# rev3.net
KiCad netlist of a schematic drawn in EAGLE
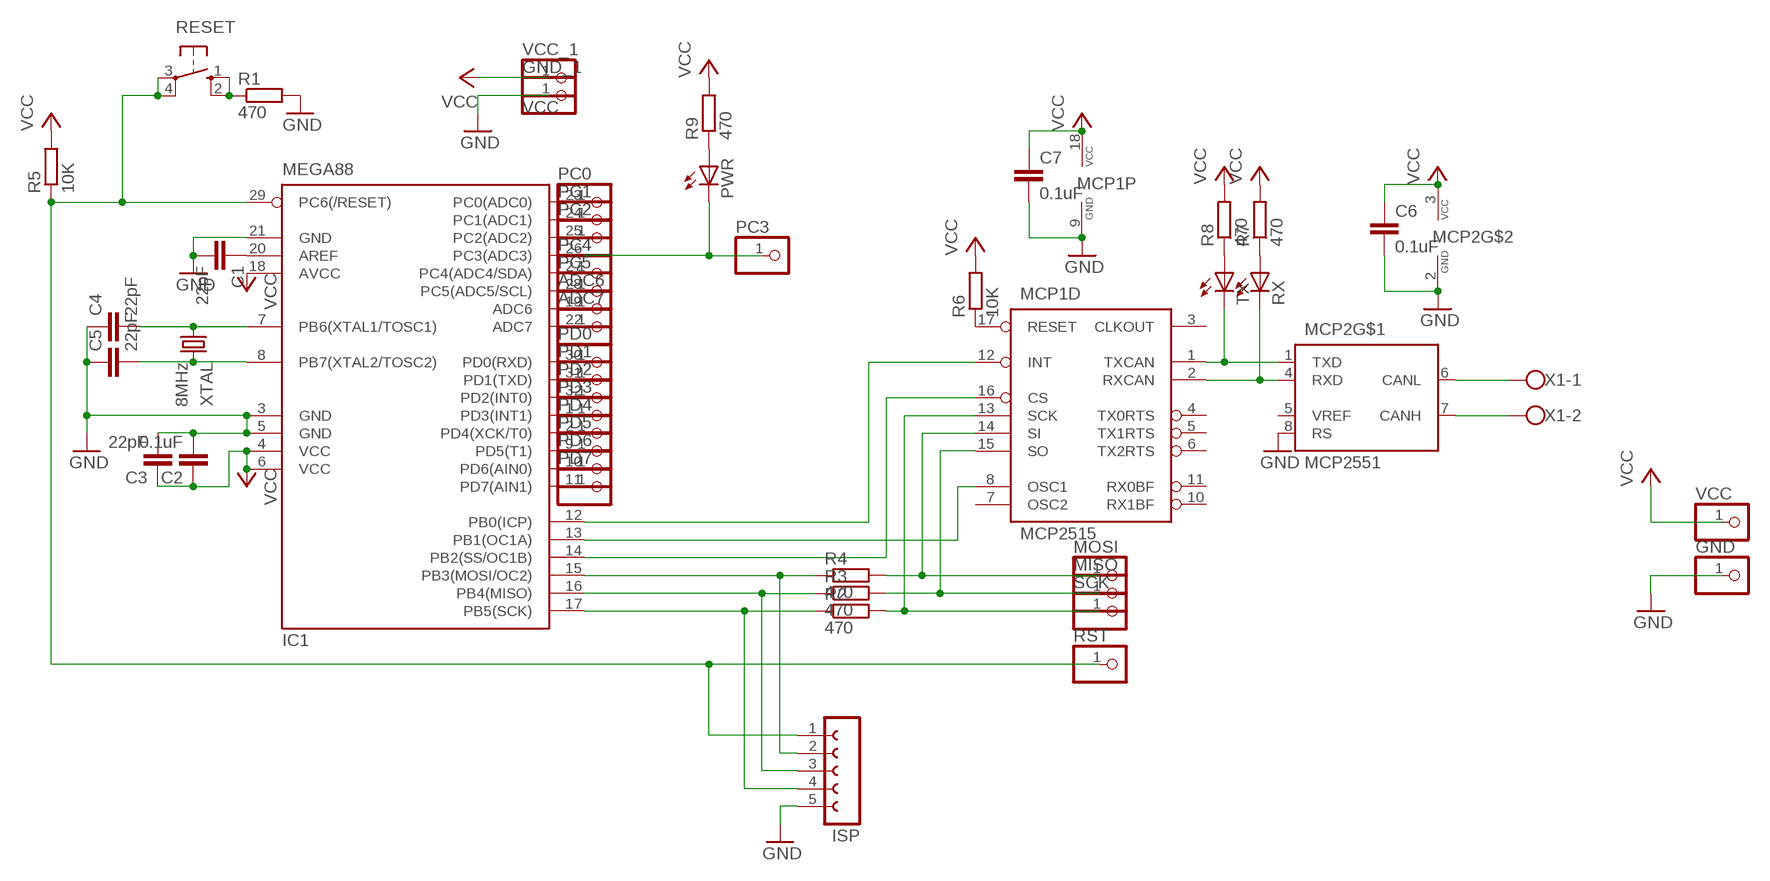
[diagram p0: schematic, sheet 1]

(export (version "E")
  (design (tool "Eeschema 10.0.6"))
  (components
    (comp (ref "ADC6")
      (value "PINHD-1X1")
      (footprint "eagle-import:1X01")
      (libsource (lib "eagle-import") (part "PINHD-1X1"))
    )
    (comp (ref "ADC7")
      (value "PINHD-1X1")
      (footprint "eagle-import:1X01")
      (libsource (lib "eagle-import") (part "PINHD-1X1"))
    )
    (comp (ref "C1")
      (value "22pF")
      (footprint "eagle-import:C0603")
      (libsource (lib "eagle-import") (part "C-EUC0603"))
    )
    (comp (ref "C2")
      (value "0.1uF")
      (footprint "eagle-import:C0603")
      (libsource (lib "eagle-import") (part "C-EUC0603"))
    )
    (comp (ref "C3")
      (value "22pF")
      (footprint "eagle-import:C0603")
      (libsource (lib "eagle-import") (part "C-EUC0603"))
    )
    (comp (ref "C4")
      (value "22pF")
      (footprint "eagle-import:C0603")
      (libsource (lib "eagle-import") (part "C-EUC0603"))
    )
    (comp (ref "C5")
      (value "22pF")
      (footprint "eagle-import:C0603")
      (libsource (lib "eagle-import") (part "C-EUC0603"))
    )
    (comp (ref "C6")
      (value "0.1uF")
      (footprint "eagle-import:C0603")
      (libsource (lib "eagle-import") (part "C-EUC0603"))
    )
    (comp (ref "C7")
      (value "0.1uF")
      (footprint "eagle-import:C0603")
      (libsource (lib "eagle-import") (part "C-EUC0603"))
    )
    (comp (ref "GND")
      (value "PINHD-1X1")
      (footprint "eagle-import:1X01")
      (libsource (lib "eagle-import") (part "PINHD-1X1"))
    )
    (comp (ref "GND_1")
      (value "PINHD-1X1")
      (footprint "eagle-import:1X01")
      (libsource (lib "eagle-import") (part "PINHD-1X1"))
    )
    (comp (ref "IC1")
      (value "MEGA88")
      (footprint "eagle-import:TQFP32-08")
      (fields (field (name "MPN") "ATMEGA8-16AU") (field (name "OC_NEWARK") "unknown"))
      (libsource (lib "eagle-import") (part "MEGA8-AI"))
    )
    (comp (ref "ISP")
      (value "FE05-1")
      (footprint "eagle-import:FE05-1")
      (libsource (lib "eagle-import") (part "FE05-1"))
    )
    (comp (ref "MCP1")
      (value "MCP2515")
      (footprint "eagle-import:DIL18")
      (fields (field (name "OC_NEWARK") "unknown"))
      (libsource (lib "eagle-import") (part "MCP2515P"))
    )
    (comp (ref "MCP2")
      (value "MCP2551")
      (footprint "eagle-import:DIL08")
      (fields (field (name "OC_NEWARK") "unknown"))
      (libsource (lib "eagle-import") (part "MCP2551DIL8"))
    )
    (comp (ref "MISO")
      (value "PINHD-1X1")
      (footprint "eagle-import:1X01")
      (libsource (lib "eagle-import") (part "PINHD-1X1"))
    )
    (comp (ref "MOSI")
      (value "PINHD-1X1")
      (footprint "eagle-import:1X01")
      (libsource (lib "eagle-import") (part "PINHD-1X1"))
    )
    (comp (ref "PC0")
      (value "PINHD-1X1")
      (footprint "eagle-import:1X01")
      (libsource (lib "eagle-import") (part "PINHD-1X1"))
    )
    (comp (ref "PC1")
      (value "PINHD-1X1")
      (footprint "eagle-import:1X01")
      (libsource (lib "eagle-import") (part "PINHD-1X1"))
    )
    (comp (ref "PC2")
      (value "PINHD-1X1")
      (footprint "eagle-import:1X01")
      (libsource (lib "eagle-import") (part "PINHD-1X1"))
    )
    (comp (ref "PC3")
      (value "PINHD-1X1")
      (footprint "eagle-import:1X01")
      (libsource (lib "eagle-import") (part "PINHD-1X1"))
    )
    (comp (ref "PC4")
      (value "PINHD-1X1")
      (footprint "eagle-import:1X01")
      (libsource (lib "eagle-import") (part "PINHD-1X1"))
    )
    (comp (ref "PC5")
      (value "PINHD-1X1")
      (footprint "eagle-import:1X01")
      (libsource (lib "eagle-import") (part "PINHD-1X1"))
    )
    (comp (ref "PD0")
      (value "PINHD-1X1")
      (footprint "eagle-import:1X01")
      (libsource (lib "eagle-import") (part "PINHD-1X1"))
    )
    (comp (ref "PD1")
      (value "PINHD-1X1")
      (footprint "eagle-import:1X01")
      (libsource (lib "eagle-import") (part "PINHD-1X1"))
    )
    (comp (ref "PD2")
      (value "PINHD-1X1")
      (footprint "eagle-import:1X01")
      (libsource (lib "eagle-import") (part "PINHD-1X1"))
    )
    (comp (ref "PD3")
      (value "PINHD-1X1")
      (footprint "eagle-import:1X01")
      (libsource (lib "eagle-import") (part "PINHD-1X1"))
    )
    (comp (ref "PD4")
      (value "PINHD-1X1")
      (footprint "eagle-import:1X01")
      (libsource (lib "eagle-import") (part "PINHD-1X1"))
    )
    (comp (ref "PD5")
      (value "PINHD-1X1")
      (footprint "eagle-import:1X01")
      (libsource (lib "eagle-import") (part "PINHD-1X1"))
    )
    (comp (ref "PD6")
      (value "PINHD-1X1")
      (footprint "eagle-import:1X01")
      (libsource (lib "eagle-import") (part "PINHD-1X1"))
    )
    (comp (ref "PD7")
      (value "PINHD-1X1")
      (footprint "eagle-import:1X01")
      (libsource (lib "eagle-import") (part "PINHD-1X1"))
    )
    (comp (ref "PWR")
      (value "LEDCHIP-LED0603")
      (footprint "eagle-import:CHIP-LED0603")
      (libsource (lib "eagle-import") (part "LEDCHIP-LED0603"))
    )
    (comp (ref "R1")
      (value "470")
      (footprint "eagle-import:R0603")
      (libsource (lib "eagle-import") (part "R-EU_R0603"))
    )
    (comp (ref "R2")
      (value "470")
      (footprint "eagle-import:R0603")
      (libsource (lib "eagle-import") (part "R-EU_R0603"))
    )
    (comp (ref "R3")
      (value "470")
      (footprint "eagle-import:R0603")
      (libsource (lib "eagle-import") (part "R-EU_R0603"))
    )
    (comp (ref "R4")
      (value "470")
      (footprint "eagle-import:R0603")
      (libsource (lib "eagle-import") (part "R-EU_R0603"))
    )
    (comp (ref "R5")
      (value "10K")
      (footprint "eagle-import:R0603")
      (libsource (lib "eagle-import") (part "R-EU_R0603"))
    )
    (comp (ref "R6")
      (value "10K")
      (footprint "eagle-import:R0603")
      (libsource (lib "eagle-import") (part "R-EU_R0603"))
    )
    (comp (ref "R7")
      (value "470")
      (footprint "eagle-import:R0603")
      (libsource (lib "eagle-import") (part "R-EU_R0603"))
    )
    (comp (ref "R8")
      (value "470")
      (footprint "eagle-import:R0603")
      (libsource (lib "eagle-import") (part "R-EU_R0603"))
    )
    (comp (ref "R9")
      (value "470")
      (footprint "eagle-import:R0603")
      (libsource (lib "eagle-import") (part "R-EU_R0603"))
    )
    (comp (ref "RESET")
      (value "10-XX")
      (footprint "eagle-import:B3F-10XX")
      (fields (field (name "MPN") "B3F-1000"))
      (libsource (lib "eagle-import") (part "10-XX"))
    )
    (comp (ref "RST")
      (value "PINHD-1X1")
      (footprint "eagle-import:1X01")
      (libsource (lib "eagle-import") (part "PINHD-1X1"))
    )
    (comp (ref "RX")
      (value "LEDCHIP-LED0603")
      (footprint "eagle-import:CHIP-LED0603")
      (libsource (lib "eagle-import") (part "LEDCHIP-LED0603"))
    )
    (comp (ref "SCK")
      (value "PINHD-1X1")
      (footprint "eagle-import:1X01")
      (libsource (lib "eagle-import") (part "PINHD-1X1"))
    )
    (comp (ref "TX")
      (value "LEDCHIP-LED0603")
      (footprint "eagle-import:CHIP-LED0603")
      (libsource (lib "eagle-import") (part "LEDCHIP-LED0603"))
    )
    (comp (ref "VCC")
      (value "PINHD-1X1")
      (footprint "eagle-import:1X01")
      (libsource (lib "eagle-import") (part "PINHD-1X1"))
    )
    (comp (ref "VCC_1")
      (value "VCC")
      (footprint "eagle-import:1X01")
      (libsource (lib "eagle-import") (part "PINHD-1X1"))
    )
    (comp (ref "X1")
      (value "W237-102")
      (footprint "eagle-import:W237-102")
      (fields (field (name "MPN") "237-102"))
      (libsource (lib "eagle-import") (part "W237-102"))
    )
    (comp (ref "XTAL")
      (value "8MHz")
      (footprint "eagle-import:HC49_S")
      (fields (field (name "OC_NEWARK") "unknown"))
      (libsource (lib "eagle-import") (part "CRYSTALHC49S"))
    )
  )
  (nets
    (net (code "1") (name "GND") (class "Default")
      (node (ref "C1") (pin "2") (pinfunction "2_2") (pintype "passive"))
      (node (ref "C2") (pin "2") (pinfunction "2_2") (pintype "passive"))
      (node (ref "C3") (pin "2") (pinfunction "2_2") (pintype "passive"))
      (node (ref "C4") (pin "1") (pinfunction "1_1") (pintype "passive"))
      (node (ref "C5") (pin "1") (pinfunction "1_1") (pintype "passive"))
      (node (ref "C6") (pin "2") (pinfunction "2_2") (pintype "passive"))
      (node (ref "C7") (pin "2") (pinfunction "2_2") (pintype "passive"))
      (node (ref "GND") (pin "1") (pinfunction "1_1") (pintype "passive"))
      (node (ref "GND_1") (pin "1") (pinfunction "1_1") (pintype "passive"))
      (node (ref "IC1") (pin "21") (pinfunction "GND_21") (pintype "power_in"))
      (node (ref "IC1") (pin "3") (pinfunction "GND_3") (pintype "power_in"))
      (node (ref "IC1") (pin "5") (pinfunction "GND_5") (pintype "power_in"))
      (node (ref "ISP") (pin "5") (pinfunction "5_5") (pintype "passive"))
      (node (ref "MCP1") (pin "9") (pinfunction "GND_9") (pintype "power_in"))
      (node (ref "MCP2") (pin "2") (pinfunction "GND_2") (pintype "power_in"))
      (node (ref "MCP2") (pin "8") (pinfunction "RS_8") (pintype "bidirectional"))
      (node (ref "R1") (pin "2") (pinfunction "2_2") (pintype "passive"))
    )
    (net (code "2") (name "Net-(IC1-ADC6)") (class "Default")
      (node (ref "ADC6") (pin "1") (pinfunction "1_1") (pintype "passive"))
      (node (ref "IC1") (pin "19") (pinfunction "ADC6_19") (pintype "bidirectional"))
    )
    (net (code "3") (name "Net-(IC1-ADC7)") (class "Default")
      (node (ref "ADC7") (pin "1") (pinfunction "1_1") (pintype "passive"))
      (node (ref "IC1") (pin "22") (pinfunction "ADC7_22") (pintype "bidirectional"))
    )
    (net (code "4") (name "Net-(IC1-AREF)") (class "Default")
      (node (ref "C1") (pin "1") (pinfunction "1_1") (pintype "passive"))
      (node (ref "IC1") (pin "20") (pinfunction "AREF_20") (pintype "passive"))
    )
    (net (code "5") (name "Net-(IC1-PB0(ICP))") (class "Default")
      (node (ref "IC1") (pin "12") (pinfunction "PB0(ICP)_12") (pintype "bidirectional"))
      (node (ref "MCP1") (pin "12") (pinfunction "INT_12") (pintype "output"))
    )
    (net (code "6") (name "Net-(IC1-PB1(OC1A))") (class "Default")
      (node (ref "IC1") (pin "13") (pinfunction "PB1(OC1A)_13") (pintype "bidirectional"))
      (node (ref "MCP1") (pin "8") (pinfunction "OSC1_8") (pintype "input"))
    )
    (net (code "7") (name "Net-(IC1-PB2(SS{slash}OC1B))") (class "Default")
      (node (ref "IC1") (pin "14") (pinfunction "PB2(SS/OC1B)_14") (pintype "bidirectional"))
      (node (ref "MCP1") (pin "16") (pinfunction "CS_16") (pintype "input"))
    )
    (net (code "8") (name "Net-(IC1-PB3(MOSI{slash}OC2))") (class "Default")
      (node (ref "IC1") (pin "15") (pinfunction "PB3(MOSI/OC2)_15") (pintype "bidirectional"))
      (node (ref "ISP") (pin "2") (pinfunction "2_2") (pintype "passive"))
      (node (ref "R4") (pin "1") (pinfunction "1_1") (pintype "passive"))
    )
    (net (code "9") (name "Net-(IC1-PB4(MISO))") (class "Default")
      (node (ref "IC1") (pin "16") (pinfunction "PB4(MISO)_16") (pintype "bidirectional"))
      (node (ref "ISP") (pin "3") (pinfunction "3_3") (pintype "passive"))
      (node (ref "R3") (pin "1") (pinfunction "1_1") (pintype "passive"))
    )
    (net (code "10") (name "Net-(IC1-PB5(SCK))") (class "Default")
      (node (ref "IC1") (pin "17") (pinfunction "PB5(SCK)_17") (pintype "bidirectional"))
      (node (ref "ISP") (pin "4") (pinfunction "4_4") (pintype "passive"))
      (node (ref "R2") (pin "1") (pinfunction "1_1") (pintype "passive"))
    )
    (net (code "11") (name "Net-(IC1-PB6(XTAL1{slash}TOSC1))") (class "Default")
      (node (ref "C4") (pin "2") (pinfunction "2_2") (pintype "passive"))
      (node (ref "IC1") (pin "7") (pinfunction "PB6(XTAL1/TOSC1)_7") (pintype "bidirectional"))
      (node (ref "XTAL") (pin "1") (pinfunction "1_1") (pintype "passive"))
    )
    (net (code "12") (name "Net-(IC1-PB7(XTAL2{slash}TOSC2))") (class "Default")
      (node (ref "C5") (pin "2") (pinfunction "2_2") (pintype "passive"))
      (node (ref "IC1") (pin "8") (pinfunction "PB7(XTAL2/TOSC2)_8") (pintype "bidirectional"))
      (node (ref "XTAL") (pin "2") (pinfunction "2_2") (pintype "passive"))
    )
    (net (code "13") (name "Net-(IC1-PC0(ADC0))") (class "Default")
      (node (ref "IC1") (pin "23") (pinfunction "PC0(ADC0)_23") (pintype "bidirectional"))
      (node (ref "PC0") (pin "1") (pinfunction "1_1") (pintype "passive"))
    )
    (net (code "14") (name "Net-(IC1-PC1(ADC1))") (class "Default")
      (node (ref "IC1") (pin "24") (pinfunction "PC1(ADC1)_24") (pintype "bidirectional"))
      (node (ref "PC1") (pin "1") (pinfunction "1_1") (pintype "passive"))
    )
    (net (code "15") (name "Net-(IC1-PC2(ADC2))") (class "Default")
      (node (ref "IC1") (pin "25") (pinfunction "PC2(ADC2)_25") (pintype "bidirectional"))
      (node (ref "PC2") (pin "1") (pinfunction "1_1") (pintype "passive"))
    )
    (net (code "16") (name "Net-(IC1-PC3(ADC3))") (class "Default")
      (node (ref "IC1") (pin "26") (pinfunction "PC3(ADC3)_26") (pintype "bidirectional"))
      (node (ref "PC3") (pin "1") (pinfunction "1_1") (pintype "passive"))
      (node (ref "PWR") (pin "C") (pinfunction "C_C") (pintype "passive"))
    )
    (net (code "17") (name "Net-(IC1-PC4(ADC4{slash}SDA))") (class "Default")
      (node (ref "IC1") (pin "27") (pinfunction "PC4(ADC4/SDA)_27") (pintype "bidirectional"))
      (node (ref "PC4") (pin "1") (pinfunction "1_1") (pintype "passive"))
    )
    (net (code "18") (name "Net-(IC1-PC5(ADC5{slash}SCL))") (class "Default")
      (node (ref "IC1") (pin "28") (pinfunction "PC5(ADC5/SCL)_28") (pintype "bidirectional"))
      (node (ref "PC5") (pin "1") (pinfunction "1_1") (pintype "passive"))
    )
    (net (code "19") (name "Net-(IC1-PC6({slash}RESET))") (class "Default")
      (node (ref "IC1") (pin "29") (pinfunction "PC6(/RESET)_29") (pintype "bidirectional"))
      (node (ref "ISP") (pin "1") (pinfunction "1_1") (pintype "passive"))
      (node (ref "R5") (pin "1") (pinfunction "1_1") (pintype "passive"))
      (node (ref "RESET") (pin "3") (pinfunction "P_3") (pintype "passive"))
      (node (ref "RESET") (pin "4") (pinfunction "P1_4") (pintype "passive"))
      (node (ref "RST") (pin "1") (pinfunction "1_1") (pintype "passive"))
    )
    (net (code "20") (name "Net-(IC1-PD0(RXD))") (class "Default")
      (node (ref "IC1") (pin "30") (pinfunction "PD0(RXD)_30") (pintype "bidirectional"))
      (node (ref "PD0") (pin "1") (pinfunction "1_1") (pintype "passive"))
    )
    (net (code "21") (name "Net-(IC1-PD1(TXD))") (class "Default")
      (node (ref "IC1") (pin "31") (pinfunction "PD1(TXD)_31") (pintype "bidirectional"))
      (node (ref "PD1") (pin "1") (pinfunction "1_1") (pintype "passive"))
    )
    (net (code "22") (name "Net-(IC1-PD2(INT0))") (class "Default")
      (node (ref "IC1") (pin "32") (pinfunction "PD2(INT0)_32") (pintype "bidirectional"))
      (node (ref "PD2") (pin "1") (pinfunction "1_1") (pintype "passive"))
    )
    (net (code "23") (name "Net-(IC1-PD3(INT1))") (class "Default")
      (node (ref "IC1") (pin "1") (pinfunction "PD3(INT1)_1") (pintype "bidirectional"))
      (node (ref "PD3") (pin "1") (pinfunction "1_1") (pintype "passive"))
    )
    (net (code "24") (name "Net-(IC1-PD4(XCK{slash}T0))") (class "Default")
      (node (ref "IC1") (pin "2") (pinfunction "PD4(XCK/T0)_2") (pintype "bidirectional"))
      (node (ref "PD4") (pin "1") (pinfunction "1_1") (pintype "passive"))
    )
    (net (code "25") (name "Net-(IC1-PD5(T1))") (class "Default")
      (node (ref "IC1") (pin "9") (pinfunction "PD5(T1)_9") (pintype "bidirectional"))
      (node (ref "PD5") (pin "1") (pinfunction "1_1") (pintype "passive"))
    )
    (net (code "26") (name "Net-(IC1-PD6(AIN0))") (class "Default")
      (node (ref "IC1") (pin "10") (pinfunction "PD6(AIN0)_10") (pintype "bidirectional"))
      (node (ref "PD6") (pin "1") (pinfunction "1_1") (pintype "passive"))
    )
    (net (code "27") (name "Net-(IC1-PD7(AIN1))") (class "Default")
      (node (ref "IC1") (pin "11") (pinfunction "PD7(AIN1)_11") (pintype "bidirectional"))
      (node (ref "PD7") (pin "1") (pinfunction "1_1") (pintype "passive"))
    )
    (net (code "28") (name "Net-(MCP1A-RESET)") (class "Default")
      (node (ref "MCP1") (pin "17") (pinfunction "RESET_17") (pintype "input"))
      (node (ref "R6") (pin "1") (pinfunction "1_1") (pintype "passive"))
    )
    (net (code "29") (name "Net-(MCP1A-RXCAN)") (class "Default")
      (node (ref "MCP1") (pin "2") (pinfunction "RXCAN_2") (pintype "input"))
      (node (ref "MCP2") (pin "4") (pinfunction "RXD_4") (pintype "bidirectional"))
      (node (ref "RX") (pin "C") (pinfunction "C_C") (pintype "passive"))
    )
    (net (code "30") (name "Net-(MCP1A-SCK)") (class "Default")
      (node (ref "MCP1") (pin "13") (pinfunction "SCK_13") (pintype "input"))
      (node (ref "R2") (pin "2") (pinfunction "2_2") (pintype "passive"))
      (node (ref "SCK") (pin "1") (pinfunction "1_1") (pintype "passive"))
    )
    (net (code "31") (name "Net-(MCP1A-SI)") (class "Default")
      (node (ref "MCP1") (pin "14") (pinfunction "SI_14") (pintype "input"))
      (node (ref "MOSI") (pin "1") (pinfunction "1_1") (pintype "passive"))
      (node (ref "R4") (pin "2") (pinfunction "2_2") (pintype "passive"))
    )
    (net (code "32") (name "Net-(MCP1A-SO)") (class "Default")
      (node (ref "MCP1") (pin "15") (pinfunction "SO_15") (pintype "output"))
      (node (ref "MISO") (pin "1") (pinfunction "1_1") (pintype "passive"))
      (node (ref "R3") (pin "2") (pinfunction "2_2") (pintype "passive"))
    )
    (net (code "33") (name "Net-(MCP1A-TXCAN)") (class "Default")
      (node (ref "MCP1") (pin "1") (pinfunction "TXCAN_1") (pintype "output"))
      (node (ref "MCP2") (pin "1") (pinfunction "TXD_1") (pintype "bidirectional"))
      (node (ref "TX") (pin "C") (pinfunction "C_C") (pintype "passive"))
    )
    (net (code "34") (name "Net-(MCP2A-CANH)") (class "Default")
      (node (ref "MCP2") (pin "7") (pinfunction "CANH_7") (pintype "bidirectional"))
      (node (ref "X1") (pin "2") (pinfunction "KL_2") (pintype "passive"))
    )
    (net (code "35") (name "Net-(MCP2A-CANL)") (class "Default")
      (node (ref "MCP2") (pin "6") (pinfunction "CANL_6") (pintype "bidirectional"))
      (node (ref "X1") (pin "1") (pinfunction "KL_1") (pintype "passive"))
    )
    (net (code "36") (name "Net-(PWR-PadA)") (class "Default")
      (node (ref "PWR") (pin "A") (pinfunction "A_A") (pintype "passive"))
      (node (ref "R9") (pin "1") (pinfunction "1_1") (pintype "passive"))
    )
    (net (code "37") (name "Net-(R7-Pad1)") (class "Default")
      (node (ref "R7") (pin "1") (pinfunction "1_1") (pintype "passive"))
      (node (ref "RX") (pin "A") (pinfunction "A_A") (pintype "passive"))
    )
    (net (code "38") (name "Net-(R8-Pad1)") (class "Default")
      (node (ref "R8") (pin "1") (pinfunction "1_1") (pintype "passive"))
      (node (ref "TX") (pin "A") (pinfunction "A_A") (pintype "passive"))
    )
    (net (code "39") (name "Net-(RESET-S)") (class "Default")
      (node (ref "R1") (pin "1") (pinfunction "1_1") (pintype "passive"))
      (node (ref "RESET") (pin "1") (pinfunction "S_1") (pintype "passive"))
      (node (ref "RESET") (pin "2") (pinfunction "S1_2") (pintype "passive"))
    )
    (net (code "40") (name "VCC") (class "Default")
      (node (ref "C2") (pin "1") (pinfunction "1_1") (pintype "passive"))
      (node (ref "C3") (pin "1") (pinfunction "1_1") (pintype "passive"))
      (node (ref "C6") (pin "1") (pinfunction "1_1") (pintype "passive"))
      (node (ref "C7") (pin "1") (pinfunction "1_1") (pintype "passive"))
      (node (ref "IC1") (pin "18") (pinfunction "AVCC_18") (pintype "power_in"))
      (node (ref "IC1") (pin "4") (pinfunction "VCC_4") (pintype "power_in"))
      (node (ref "IC1") (pin "6") (pinfunction "VCC_6") (pintype "power_in"))
      (node (ref "MCP1") (pin "18") (pinfunction "VCC_18") (pintype "power_in"))
      (node (ref "MCP2") (pin "3") (pinfunction "VCC_3") (pintype "power_in"))
      (node (ref "R5") (pin "2") (pinfunction "2_2") (pintype "passive"))
      (node (ref "R6") (pin "2") (pinfunction "2_2") (pintype "passive"))
      (node (ref "R7") (pin "2") (pinfunction "2_2") (pintype "passive"))
      (node (ref "R8") (pin "2") (pinfunction "2_2") (pintype "passive"))
      (node (ref "R9") (pin "2") (pinfunction "2_2") (pintype "passive"))
      (node (ref "VCC") (pin "1") (pinfunction "1_1") (pintype "passive"))
      (node (ref "VCC_1") (pin "1") (pinfunction "1_1") (pintype "passive"))
    )
    (net (code "41") (name "unconnected-(MCP1A-CLKOUT-Pad3)") (class "Default")
      (node (ref "MCP1") (pin "3") (pinfunction "CLKOUT_3") (pintype "output"))
    )
    (net (code "42") (name "unconnected-(MCP1A-OSC2-Pad7)") (class "Default")
      (node (ref "MCP1") (pin "7") (pinfunction "OSC2_7") (pintype "input"))
    )
    (net (code "43") (name "unconnected-(MCP1A-RX0BF-Pad11)") (class "Default")
      (node (ref "MCP1") (pin "11") (pinfunction "RX0BF_11") (pintype "output"))
    )
    (net (code "44") (name "unconnected-(MCP1A-RX1BF-Pad10)") (class "Default")
      (node (ref "MCP1") (pin "10") (pinfunction "RX1BF_10") (pintype "output"))
    )
    (net (code "45") (name "unconnected-(MCP1A-TX0RTS-Pad4)") (class "Default")
      (node (ref "MCP1") (pin "4") (pinfunction "TX0RTS_4") (pintype "input"))
    )
    (net (code "46") (name "unconnected-(MCP1A-TX1RTS-Pad5)") (class "Default")
      (node (ref "MCP1") (pin "5") (pinfunction "TX1RTS_5") (pintype "input"))
    )
    (net (code "47") (name "unconnected-(MCP1A-TX2RTS-Pad6)") (class "Default")
      (node (ref "MCP1") (pin "6") (pinfunction "TX2RTS_6") (pintype "input"))
    )
    (net (code "48") (name "unconnected-(MCP2A-VREF-Pad5)") (class "Default")
      (node (ref "MCP2") (pin "5") (pinfunction "VREF_5") (pintype "bidirectional"))
    )
  )
)
